# PowerSupply.net
KiCad netlist of a schematic drawn in EAGLE
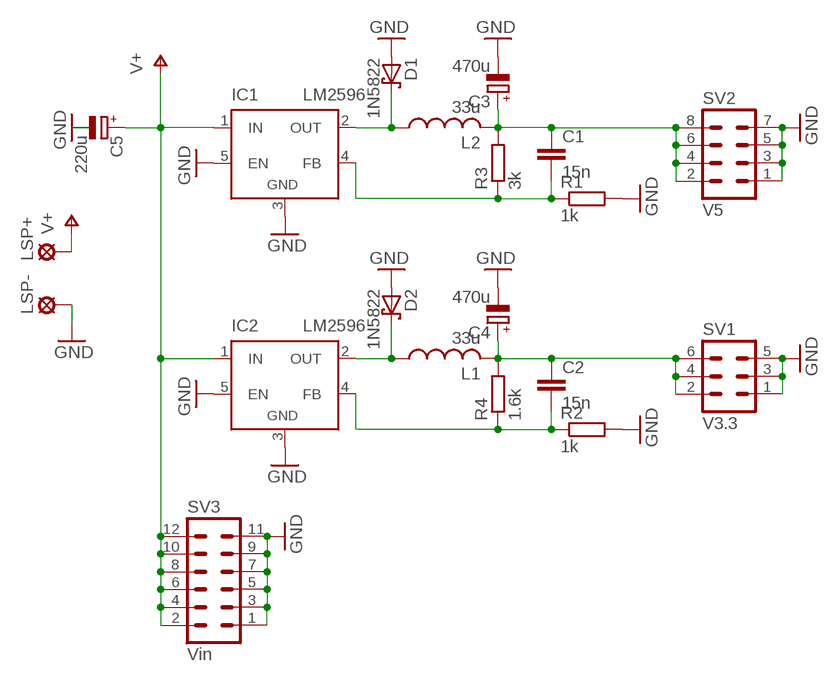
[diagram p0: schematic, sheet 1]

(export (version "E")
  (design (tool "Eeschema 10.0.6"))
  (components
    (comp (ref "C1")
      (value "15n")
      (footprint "eagle-import:C075-032X103")
      (libsource (lib "eagle-import") (part "C-EU075-032X103"))
    )
    (comp (ref "C2")
      (value "15n")
      (footprint "eagle-import:C075-032X103")
      (libsource (lib "eagle-import") (part "C-EU075-032X103"))
    )
    (comp (ref "C3")
      (value "470u")
      (footprint "eagle-import:E2,5-6")
      (libsource (lib "eagle-import") (part "CPOL-EUE2.5-6"))
    )
    (comp (ref "C4")
      (value "470u")
      (footprint "eagle-import:E2,5-6")
      (libsource (lib "eagle-import") (part "CPOL-EUE2.5-6"))
    )
    (comp (ref "C5")
      (value "220u")
      (footprint "eagle-import:E2,5-6")
      (libsource (lib "eagle-import") (part "CPOL-EUE2.5-6"))
    )
    (comp (ref "D1")
      (value "1N5822")
      (footprint "eagle-import:DO41-7.6")
      (libsource (lib "eagle-import") (part "1N5819-T"))
    )
    (comp (ref "D2")
      (value "1N5822")
      (footprint "eagle-import:DO41-7.6")
      (libsource (lib "eagle-import") (part "1N5819-T"))
    )
    (comp (ref "IC1")
      (value "LM2596")
      (footprint "eagle-import:TO220-51")
      (libsource (lib "eagle-import") (part "LM2596TV"))
    )
    (comp (ref "IC2")
      (value "LM2596")
      (footprint "eagle-import:TO220-51")
      (libsource (lib "eagle-import") (part "LM2596TV"))
    )
    (comp (ref "L1")
      (value "33u")
      (footprint "eagle-import:TFI0510")
      (libsource (lib "eagle-import") (part "L-USTFI0510"))
    )
    (comp (ref "L2")
      (value "33u")
      (footprint "eagle-import:TFI0510")
      (libsource (lib "eagle-import") (part "L-USTFI0510"))
    )
    (comp (ref "LSP+")
      (value "SE14")
      (footprint "eagle-import:SE14")
      (libsource (lib "eagle-import") (part "SE14"))
    )
    (comp (ref "LSP-")
      (value "SE14")
      (footprint "eagle-import:SE14")
      (libsource (lib "eagle-import") (part "SE14"))
    )
    (comp (ref "R1")
      (value "1k")
      (footprint "eagle-import:0309V")
      (libsource (lib "eagle-import") (part "R-EU_0309/V"))
    )
    (comp (ref "R2")
      (value "1k")
      (footprint "eagle-import:0309V")
      (libsource (lib "eagle-import") (part "R-EU_0309/V"))
    )
    (comp (ref "R3")
      (value "3k")
      (footprint "eagle-import:0204_5")
      (libsource (lib "eagle-import") (part "R-EU_0204/5"))
    )
    (comp (ref "R4")
      (value "1.6k")
      (footprint "eagle-import:0204_5")
      (libsource (lib "eagle-import") (part "R-EU_0204/5"))
    )
    (comp (ref "SV1")
      (value "V3.3")
      (footprint "eagle-import:MA03-2")
      (libsource (lib "eagle-import") (part "MA03-2"))
    )
    (comp (ref "SV2")
      (value "V5")
      (footprint "eagle-import:MA04-2")
      (libsource (lib "eagle-import") (part "MA04-2"))
    )
    (comp (ref "SV3")
      (value "Vin")
      (footprint "eagle-import:MA06-2")
      (libsource (lib "eagle-import") (part "MA06-2"))
    )
  )
  (nets
    (net (code "1") (name "GND") (class "Default")
      (node (ref "C3") (pin "-") (pinfunction "-_-") (pintype "passive"))
      (node (ref "C4") (pin "-") (pinfunction "-_-") (pintype "passive"))
      (node (ref "C5") (pin "-") (pinfunction "-_-") (pintype "passive"))
      (node (ref "D1") (pin "A") (pinfunction "A_A") (pintype "passive"))
      (node (ref "D2") (pin "A") (pinfunction "A_A") (pintype "passive"))
      (node (ref "IC1") (pin "3") (pinfunction "GND_3") (pintype "power_in"))
      (node (ref "IC1") (pin "5") (pinfunction "EN_5") (pintype "input"))
      (node (ref "IC2") (pin "3") (pinfunction "GND_3") (pintype "power_in"))
      (node (ref "IC2") (pin "5") (pinfunction "EN_5") (pintype "input"))
      (node (ref "LSP-") (pin "MP") (pinfunction "MP_MP") (pintype "passive"))
      (node (ref "R1") (pin "2") (pinfunction "2_2") (pintype "passive"))
      (node (ref "R2") (pin "2") (pinfunction "2_2") (pintype "passive"))
      (node (ref "SV1") (pin "1") (pinfunction "1_1") (pintype "passive"))
      (node (ref "SV1") (pin "3") (pinfunction "3_3") (pintype "passive"))
      (node (ref "SV1") (pin "5") (pinfunction "5_5") (pintype "passive"))
      (node (ref "SV2") (pin "1") (pinfunction "1_1") (pintype "passive"))
      (node (ref "SV2") (pin "3") (pinfunction "3_3") (pintype "passive"))
      (node (ref "SV2") (pin "5") (pinfunction "5_5") (pintype "passive"))
      (node (ref "SV2") (pin "7") (pinfunction "7_7") (pintype "passive"))
      (node (ref "SV3") (pin "1") (pinfunction "1_1") (pintype "passive"))
      (node (ref "SV3") (pin "11") (pinfunction "11_11") (pintype "passive"))
      (node (ref "SV3") (pin "3") (pinfunction "3_3") (pintype "passive"))
      (node (ref "SV3") (pin "5") (pinfunction "5_5") (pintype "passive"))
      (node (ref "SV3") (pin "7") (pinfunction "7_7") (pintype "passive"))
      (node (ref "SV3") (pin "9") (pinfunction "9_9") (pintype "passive"))
    )
    (net (code "2") (name "Net-(C1-Pad1)") (class "Default")
      (node (ref "C1") (pin "1") (pinfunction "1_1") (pintype "passive"))
      (node (ref "C3") (pin "+") (pinfunction "+_+") (pintype "passive"))
      (node (ref "L2") (pin "2") (pinfunction "2_2") (pintype "passive"))
      (node (ref "R3") (pin "2") (pinfunction "2_2") (pintype "passive"))
      (node (ref "SV2") (pin "2") (pinfunction "2_2") (pintype "passive"))
      (node (ref "SV2") (pin "4") (pinfunction "4_4") (pintype "passive"))
      (node (ref "SV2") (pin "6") (pinfunction "6_6") (pintype "passive"))
      (node (ref "SV2") (pin "8") (pinfunction "8_8") (pintype "passive"))
    )
    (net (code "3") (name "Net-(C2-Pad1)") (class "Default")
      (node (ref "C2") (pin "1") (pinfunction "1_1") (pintype "passive"))
      (node (ref "C4") (pin "+") (pinfunction "+_+") (pintype "passive"))
      (node (ref "L1") (pin "2") (pinfunction "2_2") (pintype "passive"))
      (node (ref "R4") (pin "2") (pinfunction "2_2") (pintype "passive"))
      (node (ref "SV1") (pin "2") (pinfunction "2_2") (pintype "passive"))
      (node (ref "SV1") (pin "4") (pinfunction "4_4") (pintype "passive"))
      (node (ref "SV1") (pin "6") (pinfunction "6_6") (pintype "passive"))
    )
    (net (code "4") (name "Net-(IC1-FB)") (class "Default")
      (node (ref "C1") (pin "2") (pinfunction "2_2") (pintype "passive"))
      (node (ref "IC1") (pin "4") (pinfunction "FB_4") (pintype "input"))
      (node (ref "R1") (pin "1") (pinfunction "1_1") (pintype "passive"))
      (node (ref "R3") (pin "1") (pinfunction "1_1") (pintype "passive"))
    )
    (net (code "5") (name "Net-(IC1-OUT)") (class "Default")
      (node (ref "D1") (pin "C") (pinfunction "C_C") (pintype "passive"))
      (node (ref "IC1") (pin "2") (pinfunction "OUT_2") (pintype "output"))
      (node (ref "L2") (pin "1") (pinfunction "1_1") (pintype "passive"))
    )
    (net (code "6") (name "Net-(IC2-FB)") (class "Default")
      (node (ref "C2") (pin "2") (pinfunction "2_2") (pintype "passive"))
      (node (ref "IC2") (pin "4") (pinfunction "FB_4") (pintype "input"))
      (node (ref "R2") (pin "1") (pinfunction "1_1") (pintype "passive"))
      (node (ref "R4") (pin "1") (pinfunction "1_1") (pintype "passive"))
    )
    (net (code "7") (name "Net-(IC2-OUT)") (class "Default")
      (node (ref "D2") (pin "C") (pinfunction "C_C") (pintype "passive"))
      (node (ref "IC2") (pin "2") (pinfunction "OUT_2") (pintype "output"))
      (node (ref "L1") (pin "1") (pinfunction "1_1") (pintype "passive"))
    )
    (net (code "8") (name "V+") (class "Default")
      (node (ref "C5") (pin "+") (pinfunction "+_+") (pintype "passive"))
      (node (ref "IC1") (pin "1") (pinfunction "IN_1") (pintype "input"))
      (node (ref "IC2") (pin "1") (pinfunction "IN_1") (pintype "input"))
      (node (ref "LSP+") (pin "MP") (pinfunction "MP_MP") (pintype "passive"))
      (node (ref "SV3") (pin "10") (pinfunction "10_10") (pintype "passive"))
      (node (ref "SV3") (pin "12") (pinfunction "12_12") (pintype "passive"))
      (node (ref "SV3") (pin "2") (pinfunction "2_2") (pintype "passive"))
      (node (ref "SV3") (pin "4") (pinfunction "4_4") (pintype "passive"))
      (node (ref "SV3") (pin "6") (pinfunction "6_6") (pintype "passive"))
      (node (ref "SV3") (pin "8") (pinfunction "8_8") (pintype "passive"))
    )
  )
)
